# Top_Level.net
KiCad netlist of a schematic drawn in Altium Designer
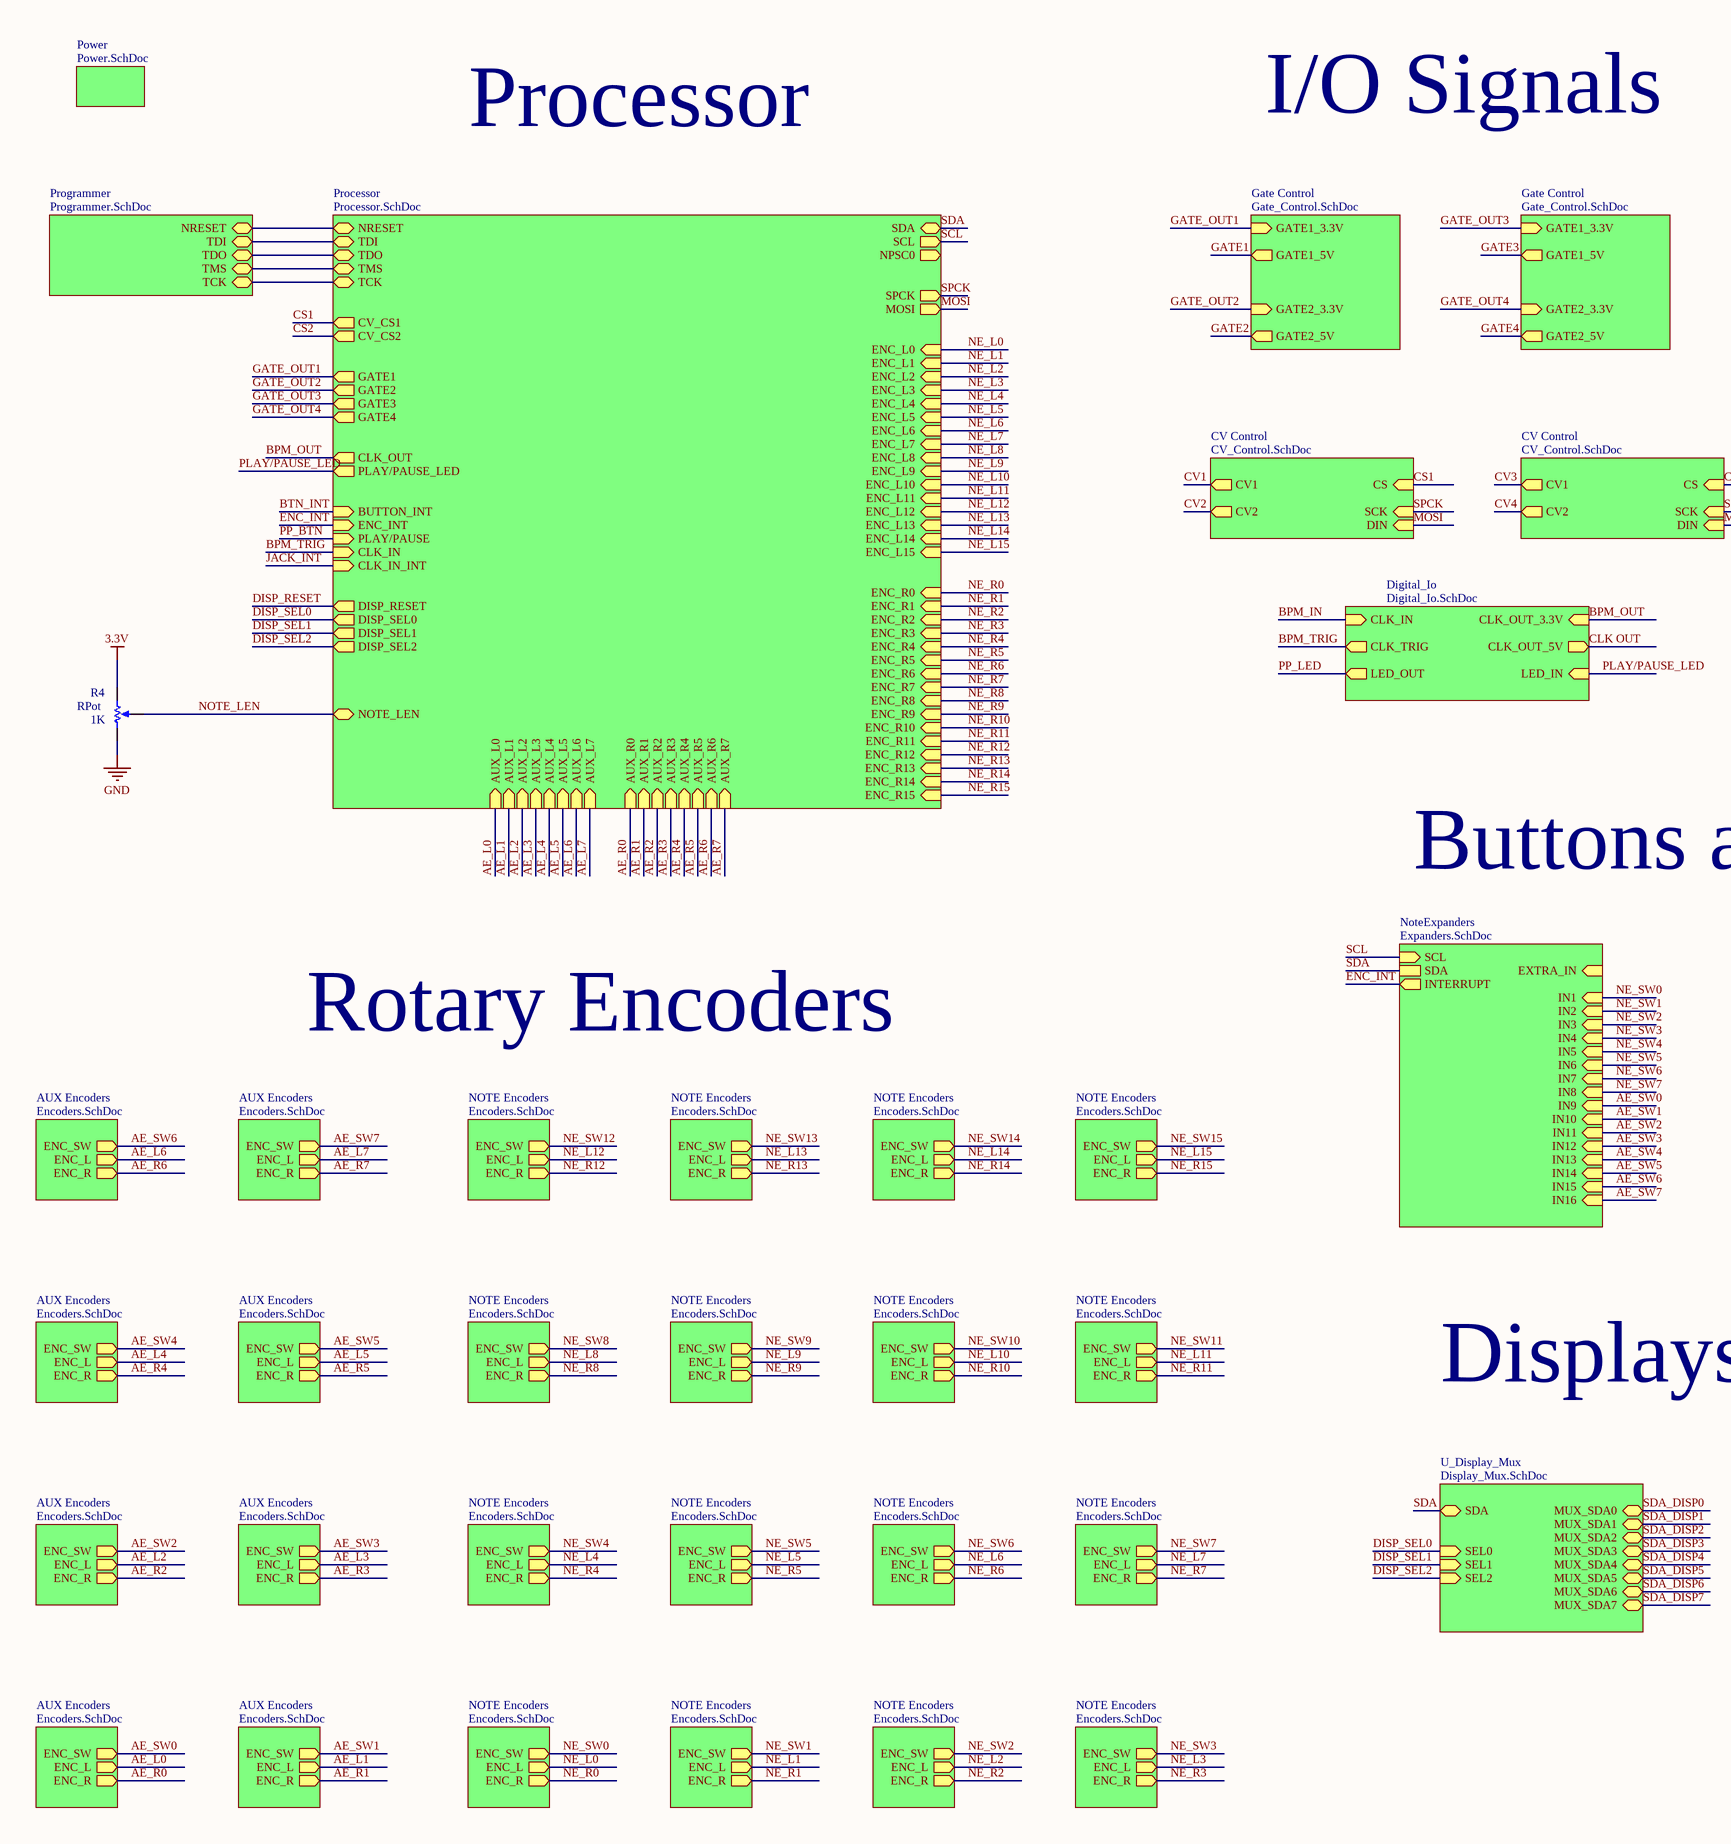
[diagram p0: Top_Level.SchDoc, left]
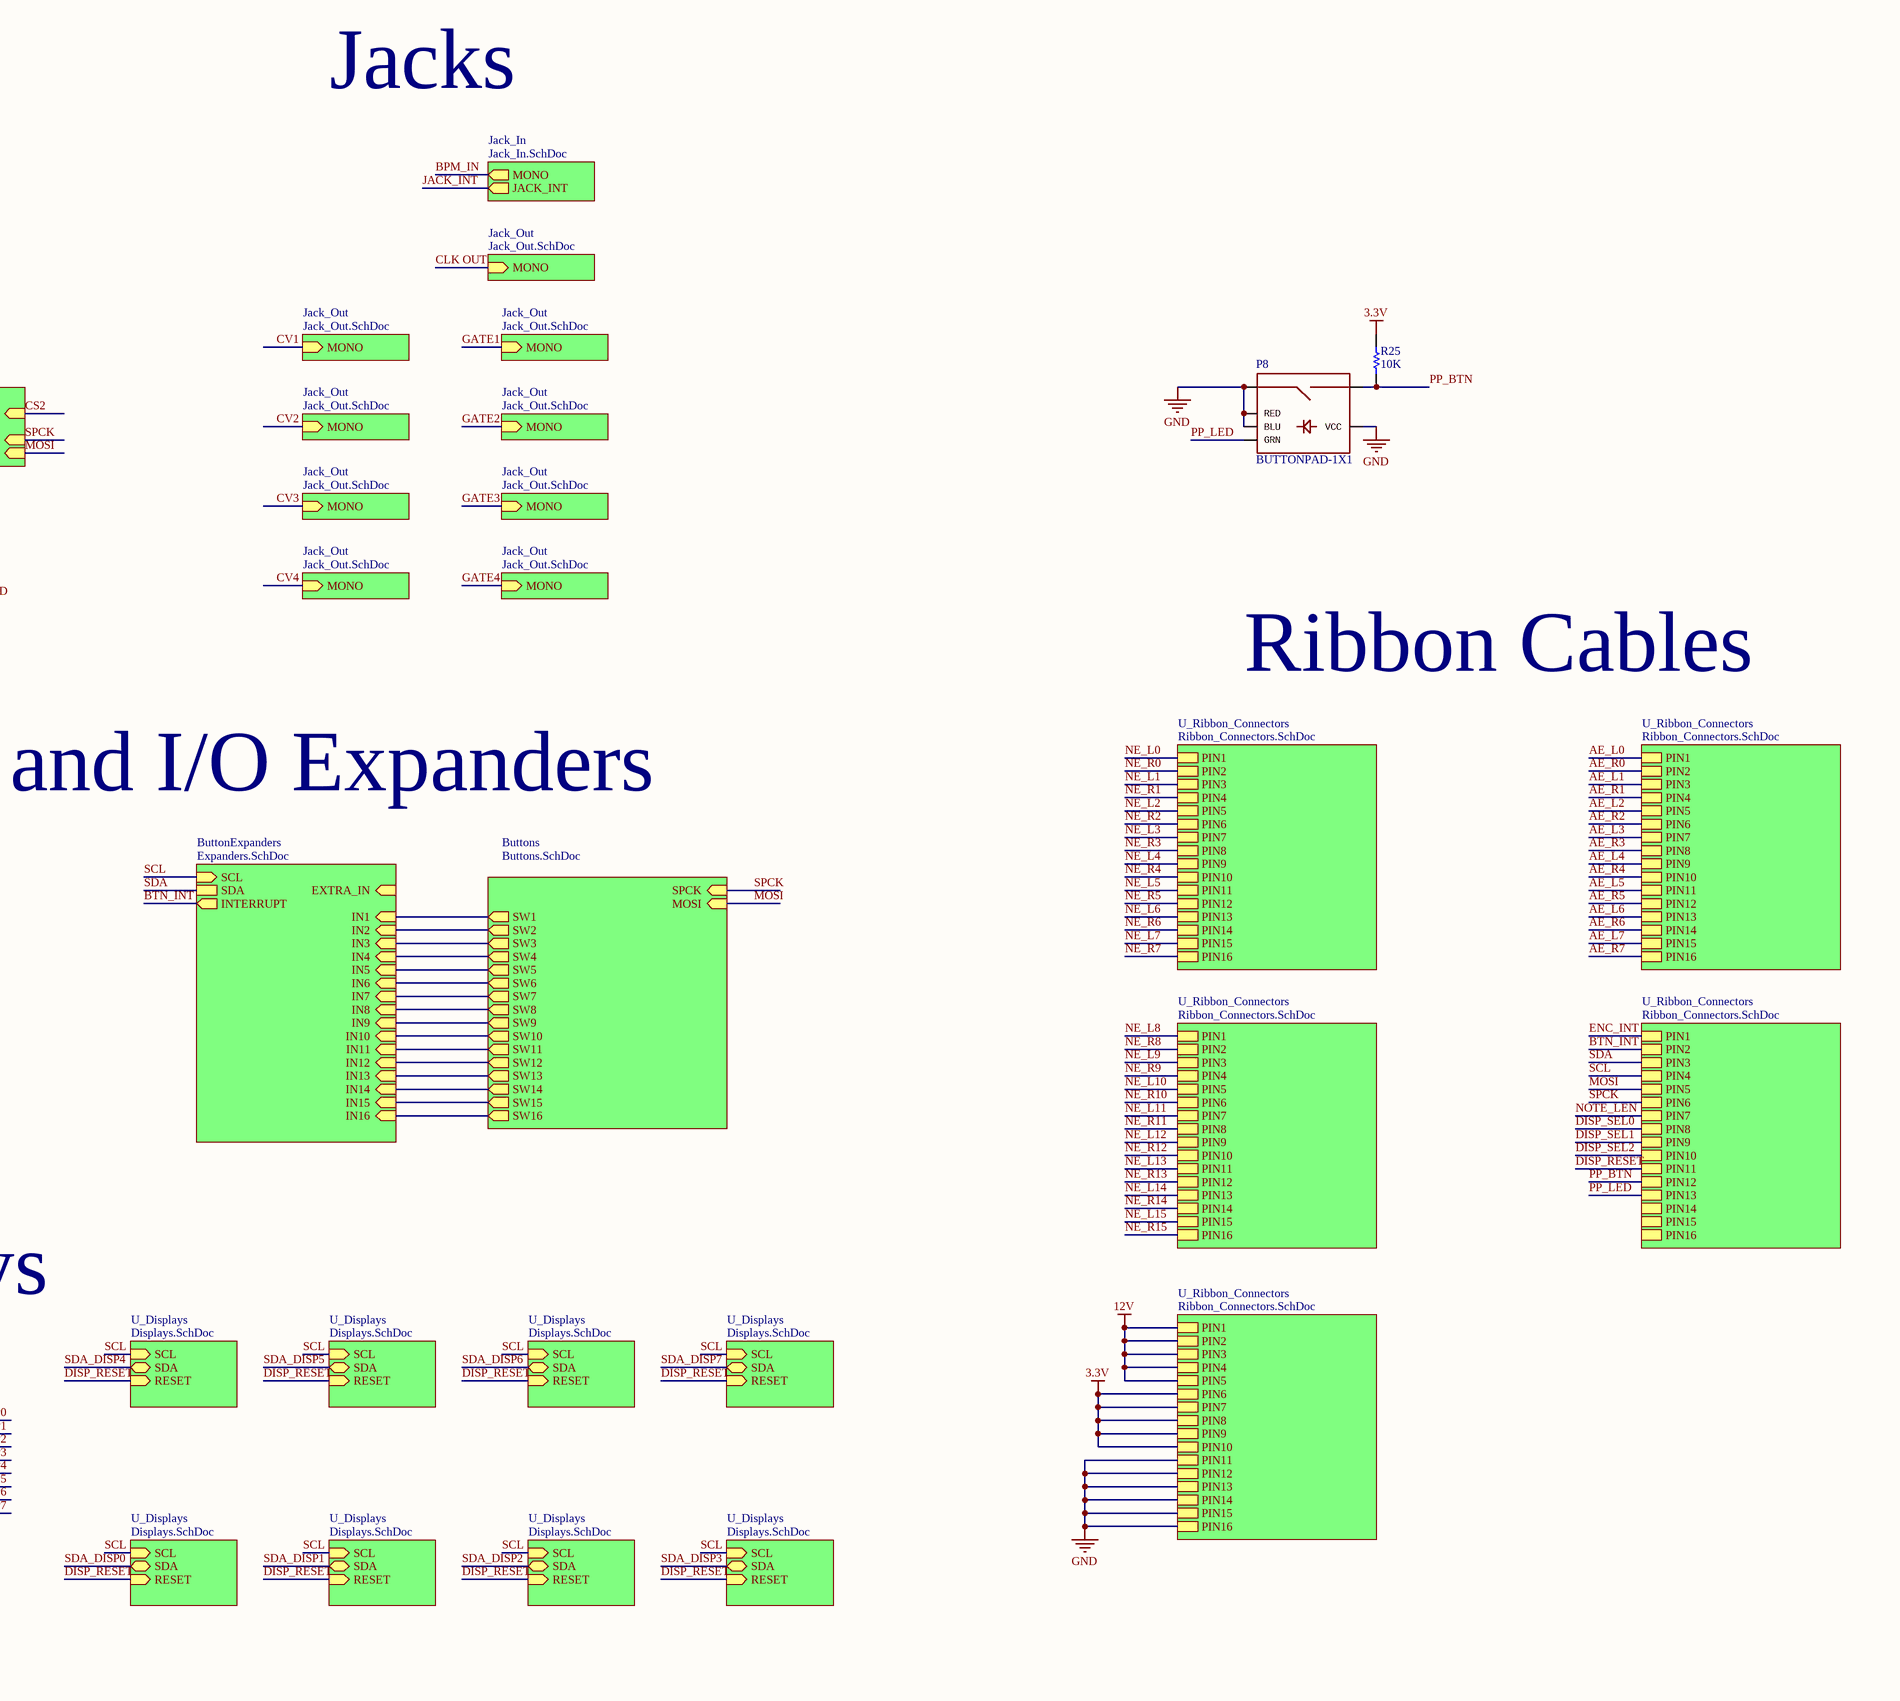
[diagram p1: Top_Level.SchDoc, right]

(export (version "E")
  (design (tool "Eeschema 10.0.6"))
  (components
    (comp (ref "P8")
      (value "BUTTONPAD-1X1")
      (footprint "BUTTONPAD-1X1")
      (libsource (lib "Button_Pad_Breakout-v05") (part "BUTTONPAD-1X1"))
    )
    (comp (ref "R4")
      (value "RPot")
      (footprint "POT inline wide")
      (description "Potentiometer")
      (fields (field (name "ALTIUM_VALUE") "1K") (field (name "PUBLISHER") "Altium Limited"))
      (libsource (lib "Miscellaneous Devices") (part "RPot"))
    )
    (comp (ref "R25")
      (value "10K")
      (footprint "AXIAL-0.3")
      (description "Resistor")
      (fields (field (name "Comment") "R3") (field (name "PUBLISHER") "Altium Limited"))
      (libsource (lib "Miscellaneous Devices") (part "Res1"))
    )
  )
  (nets
    (net (code "101") (name "/NOTE_LEN") (class "Default")
      (node (ref "R4") (pin "3") (pinfunction "TAP_3") (pintype "passive"))
    )
    (net (code "108") (name "/PP_BTN") (class "Default")
      (node (ref "P8") (pin "SIG2") (pinfunction "SIG2_SIG2") (pintype "passive"))
      (node (ref "R25") (pin "1") (pinfunction "1_1") (pintype "passive"))
    )
    (net (code "109") (name "/PP_LED") (class "Default")
      (node (ref "P8") (pin "GRN1") (pinfunction "GRN_GRN1") (pintype "passive"))
    )
    (net (code "141") (name "3.3V") (class "Default")
      (node (ref "R25") (pin "2") (pinfunction "2_2") (pintype "passive"))
      (node (ref "R4") (pin "2") (pinfunction "BOT_2") (pintype "passive"))
    )
    (net (code "143") (name "GND") (class "Default")
      (node (ref "P8") (pin "BLU1") (pinfunction "BLU_BLU1") (pintype "passive"))
      (node (ref "P8") (pin "RED1") (pinfunction "RED_RED1") (pintype "passive"))
      (node (ref "P8") (pin "SIG1") (pinfunction "SIG1_SIG1") (pintype "passive"))
      (node (ref "P8") (pin "VCC1") (pinfunction "VCC_VCC1") (pintype "passive"))
      (node (ref "R4") (pin "1") (pinfunction "TOP_1") (pintype "passive"))
    )
  )
)
